# ne555.net
KiCad netlist of a schematic drawn in Altium Designer
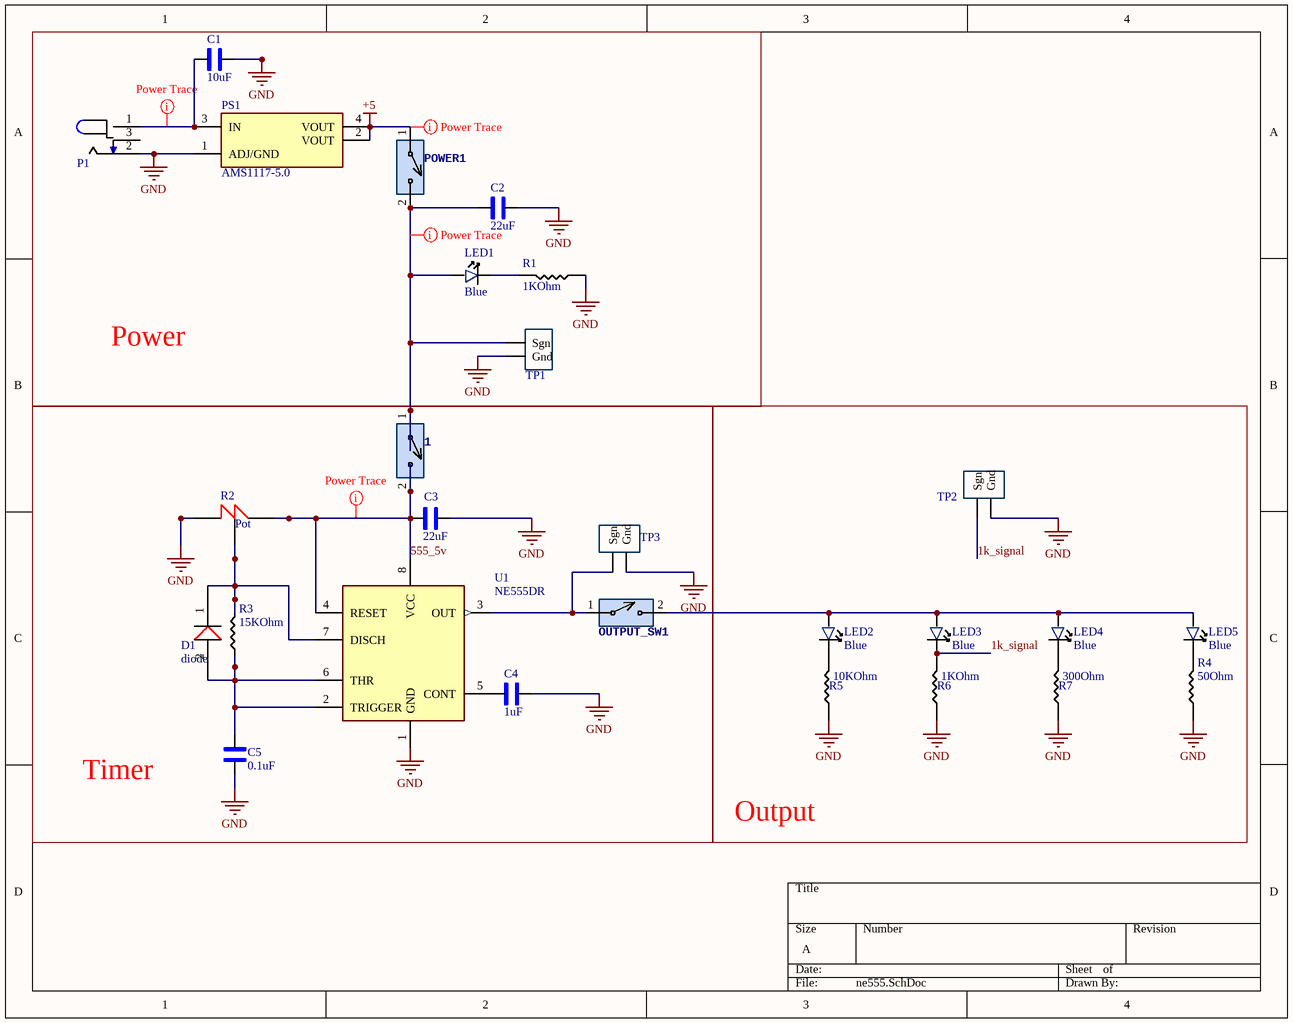
[diagram p0: ne555.SchDoc]

(export (version "E")
  (design (tool "Eeschema 10.0.6"))
  (components
    (comp (ref "1")
      (value "SW_2Pin_100mil_Switch")
      (footprint "2Pin-Header-Conn")
      (description "2Pin Header")
      (fields (field (name "LCSC PART#") "C124375"))
      (libsource (lib "ECEN5730Lib_2023_05_DS") (part "SW_2Pin_100mil_Switch"))
    )
    (comp (ref "C1")
      (value "10uF")
      (footprint "1206_Passive_Capacitor")
      (description "MULTILAYER CERAMIC CAPACITORS MLCC - SMD/SMT 1UF 50V 1206 ROHS")
      (fields (field (name "MFR PART #") "CL31B105KBHNNNE") (field (name "LCSC PART#") "C1848"))
      (libsource (lib "ECEN5730Lib_2023_05_DS") (part "C_1uF_1206"))
    )
    (comp (ref "C2")
      (value "22uF")
      (footprint "1206_Passive_Capacitor")
      (description "MULTILAYER CERAMIC CAPACITORS MLCC - SMD/SMT 1UF 50V 1206 ROHS")
      (fields (field (name "MFR PART #") "CL31B105KBHNNNE") (field (name "LCSC PART#") "C1848"))
      (libsource (lib "ECEN5730Lib_2023_05_DS") (part "C_1uF_1206"))
    )
    (comp (ref "C3")
      (value "22uF")
      (footprint "1206_Passive_Capacitor")
      (description "MULTILAYER CERAMIC CAPACITORS MLCC - SMD/SMT 1UF 50V 1206 ROHS")
      (fields (field (name "MFR PART #") "CL31B105KBHNNNE") (field (name "LCSC PART#") "C1848"))
      (libsource (lib "ECEN5730Lib_2023_05_DS") (part "C_1uF_1206"))
    )
    (comp (ref "C4")
      (value "1uF")
      (footprint "1206_Passive_Capacitor")
      (description "MULTILAYER CERAMIC CAPACITORS MLCC - SMD/SMT 1UF 50V 1206 ROHS")
      (fields (field (name "MFR PART #") "CL31B105KBHNNNE") (field (name "LCSC PART#") "C1848"))
      (libsource (lib "ECEN5730Lib_2023_05_DS") (part "C_1uF_1206"))
    )
    (comp (ref "C5")
      (value "0.1uF")
      (footprint "1206_Passive_Capacitor")
      (description "MULTILAYER CERAMIC CAPACITORS MLCC - SMD/SMT 1UF 50V 1206 ROHS")
      (fields (field (name "MFR PART #") "CL31B105KBHNNNE") (field (name "LCSC PART#") "C1848"))
      (libsource (lib "ECEN5730Lib_2023_05_DS") (part "C_1uF_1206"))
    )
    (comp (ref "D1")
      (value "diode")
      (footprint "Through hole diode")
      (libsource (lib "ne555") (part "diode"))
    )
    (comp (ref "LED1")
      (value "Blue")
      (footprint "LED_1206")
      (description "blue 1206  Light Emitting Diodes (LED) ROHS")
      (fields (field (name "MFR PART #") "NCD1206B1") (field (name "LCSC PART#") "C130717"))
      (libsource (lib "ECEN5730Lib_2023_05_DS") (part "LED_BLUE_1206"))
    )
    (comp (ref "LED2")
      (value "Blue")
      (footprint "LED_1206")
      (description "blue 1206  Light Emitting Diodes (LED) ROHS")
      (fields (field (name "MFR PART #") "NCD1206B1") (field (name "LCSC PART#") "C130717"))
      (libsource (lib "ECEN5730Lib_2023_05_DS") (part "LED_BLUE_1206"))
    )
    (comp (ref "LED3")
      (value "Blue")
      (footprint "LED_1206")
      (description "blue 1206  Light Emitting Diodes (LED) ROHS")
      (fields (field (name "MFR PART #") "NCD1206B1") (field (name "LCSC PART#") "C130717"))
      (libsource (lib "ECEN5730Lib_2023_05_DS") (part "LED_BLUE_1206"))
    )
    (comp (ref "LED4")
      (value "Blue")
      (footprint "LED_1206")
      (description "blue 1206  Light Emitting Diodes (LED) ROHS")
      (fields (field (name "MFR PART #") "NCD1206B1") (field (name "LCSC PART#") "C130717"))
      (libsource (lib "ECEN5730Lib_2023_05_DS") (part "LED_BLUE_1206"))
    )
    (comp (ref "LED5")
      (value "Blue")
      (footprint "LED_1206")
      (description "blue 1206  Light Emitting Diodes (LED) ROHS")
      (fields (field (name "MFR PART #") "NCD1206B1") (field (name "LCSC PART#") "C130717"))
      (libsource (lib "ECEN5730Lib_2023_05_DS") (part "LED_BLUE_1206"))
    )
    (comp (ref "OUTPUT_SW1")
      (value "SW_2Pin_100mil_Switch")
      (footprint "2Pin-Header-Conn")
      (description "2Pin Header")
      (fields (field (name "LCSC PART#") "C124375"))
      (libsource (lib "") (part "SW_2Pin_100mil_Switch_1"))
    )
    (comp (ref "P1")
      (value "Power Jack")
      (footprint "Power_Jack")
      (description "Power Barrel Connector Jack 2.10mm ID (0.083\"), 5.50mm OD (0.217\") Through Hole, Right Angle")
      (fields (field (name "MFR PART #") "PJ-102A") (field (name "LCSC PART#") "C136744"))
      (libsource (lib "ECEN5730Lib_2023_05_DS") (part "P_Power Jack"))
    )
    (comp (ref "POWER1")
      (value "SW_2Pin_100mil_Switch")
      (footprint "2Pin-Header-Conn")
      (description "2Pin Header")
      (fields (field (name "LCSC PART#") "C124375"))
      (libsource (lib "ECEN5730Lib_2023_05_DS") (part "SW_2Pin_100mil_Switch"))
    )
    (comp (ref "PS1")
      (value "AMS1117-5.0")
      (footprint "LDO")
      (description "LOW DROPOUT REGULATORS(LDO) POSITIVE FIXED 1.3V @ 1A 15V 5V 1A SOT-223 ROHS")
      (fields (field (name "LCSC PART#") "C6187"))
      (libsource (lib "ECEN5730Lib_2023_05_DS") (part "PS_AMS_LDO_5V"))
    )
    (comp (ref "R1")
      (value "1KOhm")
      (footprint "1206_Passive_Resitor")
      (description "1kΩ ±1% 0.25W ±100ppm/℃ 1206 Chip Resistor - Surface Mount RoHS")
      (fields (field (name "LCSC PART#") "C17936") (field (name "MFR PART #") "1206W4F4701T5E"))
      (libsource (lib "ECEN5730Lib_2023_05_DS") (part "R_4.7k_1206"))
    )
    (comp (ref "R2")
      (value "Pot")
      (footprint "potentiometer")
      (description "3 pin potentiometer, Through hole component")
      (libsource (lib "ne555") (part "Potentiometer"))
    )
    (comp (ref "R3")
      (value "15KOhm")
      (footprint "1206_Passive_Resitor")
      (description "4.7kΩ ±1% 0.25W ±100ppm/℃ 1206 Chip Resistor - Surface Mount RoHS")
      (fields (field (name "LCSC PART#") "C17936") (field (name "MFR PART #") "1206W4F4701T5E"))
      (libsource (lib "ECEN5730Lib_2023_05_DS") (part "R_4.7k_1206"))
    )
    (comp (ref "R4")
      (value "50Ohm")
      (footprint "1206_Passive_Resitor")
      (description "50Ω ±1% 0.25W ±100ppm/℃ 1206 Chip Resistor - Surface Mount RoHS")
      (fields (field (name "LCSC PART#") "C17936") (field (name "MFR PART #") "1206W4F4701T5E"))
      (libsource (lib "ECEN5730Lib_2023_05_DS") (part "R_4.7k_1206"))
    )
    (comp (ref "R5")
      (value "10KOhm")
      (footprint "1206_Passive_Resitor")
      (description "4.7kΩ ±1% 0.25W ±100ppm/℃ 1206 Chip Resistor - Surface Mount RoHS")
      (fields (field (name "LCSC PART#") "C17936") (field (name "MFR PART #") "1206W4F4701T5E"))
      (libsource (lib "ECEN5730Lib_2023_05_DS") (part "R_4.7k_1206"))
    )
    (comp (ref "R6")
      (value "1KOhm")
      (footprint "1206_Passive_Resitor")
      (description "1kΩ ±1% 0.25W ±100ppm/℃ 1206 Chip Resistor - Surface Mount RoHS")
      (fields (field (name "LCSC PART#") "C17936") (field (name "MFR PART #") "1206W4F4701T5E"))
      (libsource (lib "ECEN5730Lib_2023_05_DS") (part "R_4.7k_1206"))
    )
    (comp (ref "R7")
      (value "300Ohm")
      (footprint "1206_Passive_Resitor")
      (description "300Ω ±1% 0.25W ±100ppm/℃ 1206 Chip Resistor - Surface Mount RoHS")
      (fields (field (name "LCSC PART#") "C17936") (field (name "MFR PART #") "1206W4F4701T5E"))
      (libsource (lib "ECEN5730Lib_2023_05_DS") (part "R_4.7k_1206"))
    )
    (comp (ref "TP1")
      (value "10x Probe TP")
      (footprint "TP10x_Probe")
      (description "Test Point 300 mil centers")
      (libsource (lib "") (part "TP_10x_Probe_1"))
    )
    (comp (ref "TP2")
      (value "LED Test probe")
      (footprint "TP10x_Probe")
      (description "Test Point 300 mil centers")
      (libsource (lib "ECEN5730Lib_2023_05_DS") (part "TP_10x_Probe"))
    )
    (comp (ref "TP3")
      (value "10x Probe TP")
      (footprint "TP10x_Probe")
      (description "Test Point 300 mil centers")
      (libsource (lib "ECEN5730Lib_2023_05_DS") (part "TP_10x_Probe"))
    )
    (comp (ref "U1")
      (value "NE555DR")
      (footprint "TS555IDTTR")
      (description "555 Timer SOIC-8_150MIL ROHS 150ns Rise Time")
      (fields (field (name "LCSC PART#") "C7593"))
      (libsource (lib "ECEN5730Lib_2023_05_DS") (part "U_555_Slow"))
    )
  )
  (nets
    (net (code "1") (name "+5") (class "Default")
      (node (ref "POWER1") (pin "1") (pinfunction "1_1") (pintype "passive"))
      (node (ref "PS1") (pin "2") (pinfunction "VOUT_2") (pintype "power_in"))
      (node (ref "PS1") (pin "4") (pinfunction "VOUT_4") (pintype "power_in"))
    )
    (net (code "2") (name "/1k_signal") (class "Default")
      (node (ref "LED3") (pin "2") (pinfunction "2_2") (pintype "passive"))
      (node (ref "R6") (pin "2") (pinfunction "2_2") (pintype "passive"))
      (node (ref "TP2") (pin "1") (pinfunction "Sgn_1") (pintype "passive"))
    )
    (net (code "3") (name "/555_5v") (class "Default")
      (node (ref "1") (pin "2") (pinfunction "2_2") (pintype "passive"))
      (node (ref "C3") (pin "2") (pinfunction "2_2") (pintype "passive"))
      (node (ref "R2") (pin "2") (pinfunction "2_2") (pintype "passive"))
      (node (ref "U1") (pin "4") (pinfunction "RESET_4") (pintype "passive"))
      (node (ref "U1") (pin "8") (pinfunction "VCC_8") (pintype "power_in"))
    )
    (net (code "4") (name "GND") (class "Default")
      (node (ref "C1") (pin "2") (pinfunction "2_2") (pintype "passive"))
      (node (ref "C2") (pin "1") (pinfunction "1_1") (pintype "passive"))
      (node (ref "C3") (pin "1") (pinfunction "1_1") (pintype "passive"))
      (node (ref "C4") (pin "1") (pinfunction "1_1") (pintype "passive"))
      (node (ref "C5") (pin "1") (pinfunction "1_1") (pintype "passive"))
      (node (ref "P1") (pin "2") (pinfunction "2_2") (pintype "power_in"))
      (node (ref "PS1") (pin "1") (pinfunction "ADJ/GND_1") (pintype "passive"))
      (node (ref "R1") (pin "1") (pinfunction "1_1") (pintype "passive"))
      (node (ref "R2") (pin "1") (pinfunction "1_1") (pintype "passive"))
      (node (ref "R4") (pin "1") (pinfunction "1_1") (pintype "passive"))
      (node (ref "R5") (pin "1") (pinfunction "1_1") (pintype "passive"))
      (node (ref "R6") (pin "1") (pinfunction "1_1") (pintype "passive"))
      (node (ref "R7") (pin "1") (pinfunction "1_1") (pintype "passive"))
      (node (ref "TP1") (pin "2") (pinfunction "Gnd_2") (pintype "passive"))
      (node (ref "TP2") (pin "2") (pinfunction "Gnd_2") (pintype "passive"))
      (node (ref "TP3") (pin "2") (pinfunction "Gnd_2") (pintype "passive"))
      (node (ref "U1") (pin "1") (pinfunction "GND_1") (pintype "power_in"))
    )
    (net (code "5") (name "Net-(LED1-Pad2)") (class "Default")
      (node (ref "LED1") (pin "2") (pinfunction "2_2") (pintype "passive"))
      (node (ref "R1") (pin "2") (pinfunction "2_2") (pintype "passive"))
    )
    (net (code "6") (name "Net-(LED2-Pad1)") (class "Default")
      (node (ref "LED2") (pin "1") (pinfunction "1_1") (pintype "passive"))
      (node (ref "LED3") (pin "1") (pinfunction "1_1") (pintype "passive"))
      (node (ref "LED4") (pin "1") (pinfunction "1_1") (pintype "passive"))
      (node (ref "LED5") (pin "1") (pinfunction "1_1") (pintype "passive"))
      (node (ref "OUTPUT_SW1") (pin "2") (pinfunction "2_2") (pintype "passive"))
    )
    (net (code "7") (name "Net-(LED2-Pad2)") (class "Default")
      (node (ref "LED2") (pin "2") (pinfunction "2_2") (pintype "passive"))
      (node (ref "R5") (pin "2") (pinfunction "2_2") (pintype "passive"))
    )
    (net (code "8") (name "Net-(LED4-Pad2)") (class "Default")
      (node (ref "LED4") (pin "2") (pinfunction "2_2") (pintype "passive"))
      (node (ref "R7") (pin "2") (pinfunction "2_2") (pintype "passive"))
    )
    (net (code "9") (name "Net-(LED5-Pad2)") (class "Default")
      (node (ref "LED5") (pin "2") (pinfunction "2_2") (pintype "passive"))
      (node (ref "R4") (pin "2") (pinfunction "2_2") (pintype "passive"))
    )
    (net (code "10") (name "Net-(PS1-IN)") (class "Default")
      (node (ref "C1") (pin "1") (pinfunction "1_1") (pintype "passive"))
      (node (ref "P1") (pin "1") (pinfunction "1_1") (pintype "power_in"))
      (node (ref "PS1") (pin "3") (pinfunction "IN_3") (pintype "power_in"))
    )
    (net (code "11") (name "Net-(TP1-Sgn)") (class "Default")
      (node (ref "1") (pin "1") (pinfunction "1_1") (pintype "passive"))
      (node (ref "C2") (pin "2") (pinfunction "2_2") (pintype "passive"))
      (node (ref "LED1") (pin "1") (pinfunction "1_1") (pintype "passive"))
      (node (ref "POWER1") (pin "2") (pinfunction "2_2") (pintype "passive"))
      (node (ref "TP1") (pin "1") (pinfunction "Sgn_1") (pintype "passive"))
    )
    (net (code "12") (name "Net-(TP3-Sgn)") (class "Default")
      (node (ref "OUTPUT_SW1") (pin "1") (pinfunction "1_1") (pintype "passive"))
      (node (ref "TP3") (pin "1") (pinfunction "Sgn_1") (pintype "passive"))
      (node (ref "U1") (pin "3") (pinfunction "OUT_3") (pintype "output"))
    )
    (net (code "13") (name "Net-(U1-CONT)") (class "Default")
      (node (ref "C4") (pin "2") (pinfunction "2_2") (pintype "passive"))
      (node (ref "U1") (pin "5") (pinfunction "CONT_5") (pintype "passive"))
    )
    (net (code "14") (name "Net-(U1-DISCH)") (class "Default")
      (node (ref "D1") (pin "1") (pinfunction "1_1") (pintype "passive"))
      (node (ref "R2") (pin "3") (pinfunction "3_3") (pintype "passive"))
      (node (ref "R3") (pin "2") (pinfunction "2_2") (pintype "passive"))
      (node (ref "U1") (pin "7") (pinfunction "DISCH_7") (pintype "passive"))
    )
    (net (code "15") (name "Net-(U1-THR)") (class "Default")
      (node (ref "C5") (pin "2") (pinfunction "2_2") (pintype "passive"))
      (node (ref "D1") (pin "2") (pinfunction "2_2") (pintype "passive"))
      (node (ref "R3") (pin "1") (pinfunction "1_1") (pintype "passive"))
      (node (ref "U1") (pin "2") (pinfunction "TRIGGER_2") (pintype "passive"))
      (node (ref "U1") (pin "6") (pinfunction "THR_6") (pintype "passive"))
    )
    (net (code "16") (name "unconnected-(P1-Pad3)") (class "Default")
      (node (ref "P1") (pin "3") (pinfunction "3_3") (pintype "power_in"))
    )
  )
)
